# Water_SCH.net
KiCad netlist of a schematic drawn in Altium Designer
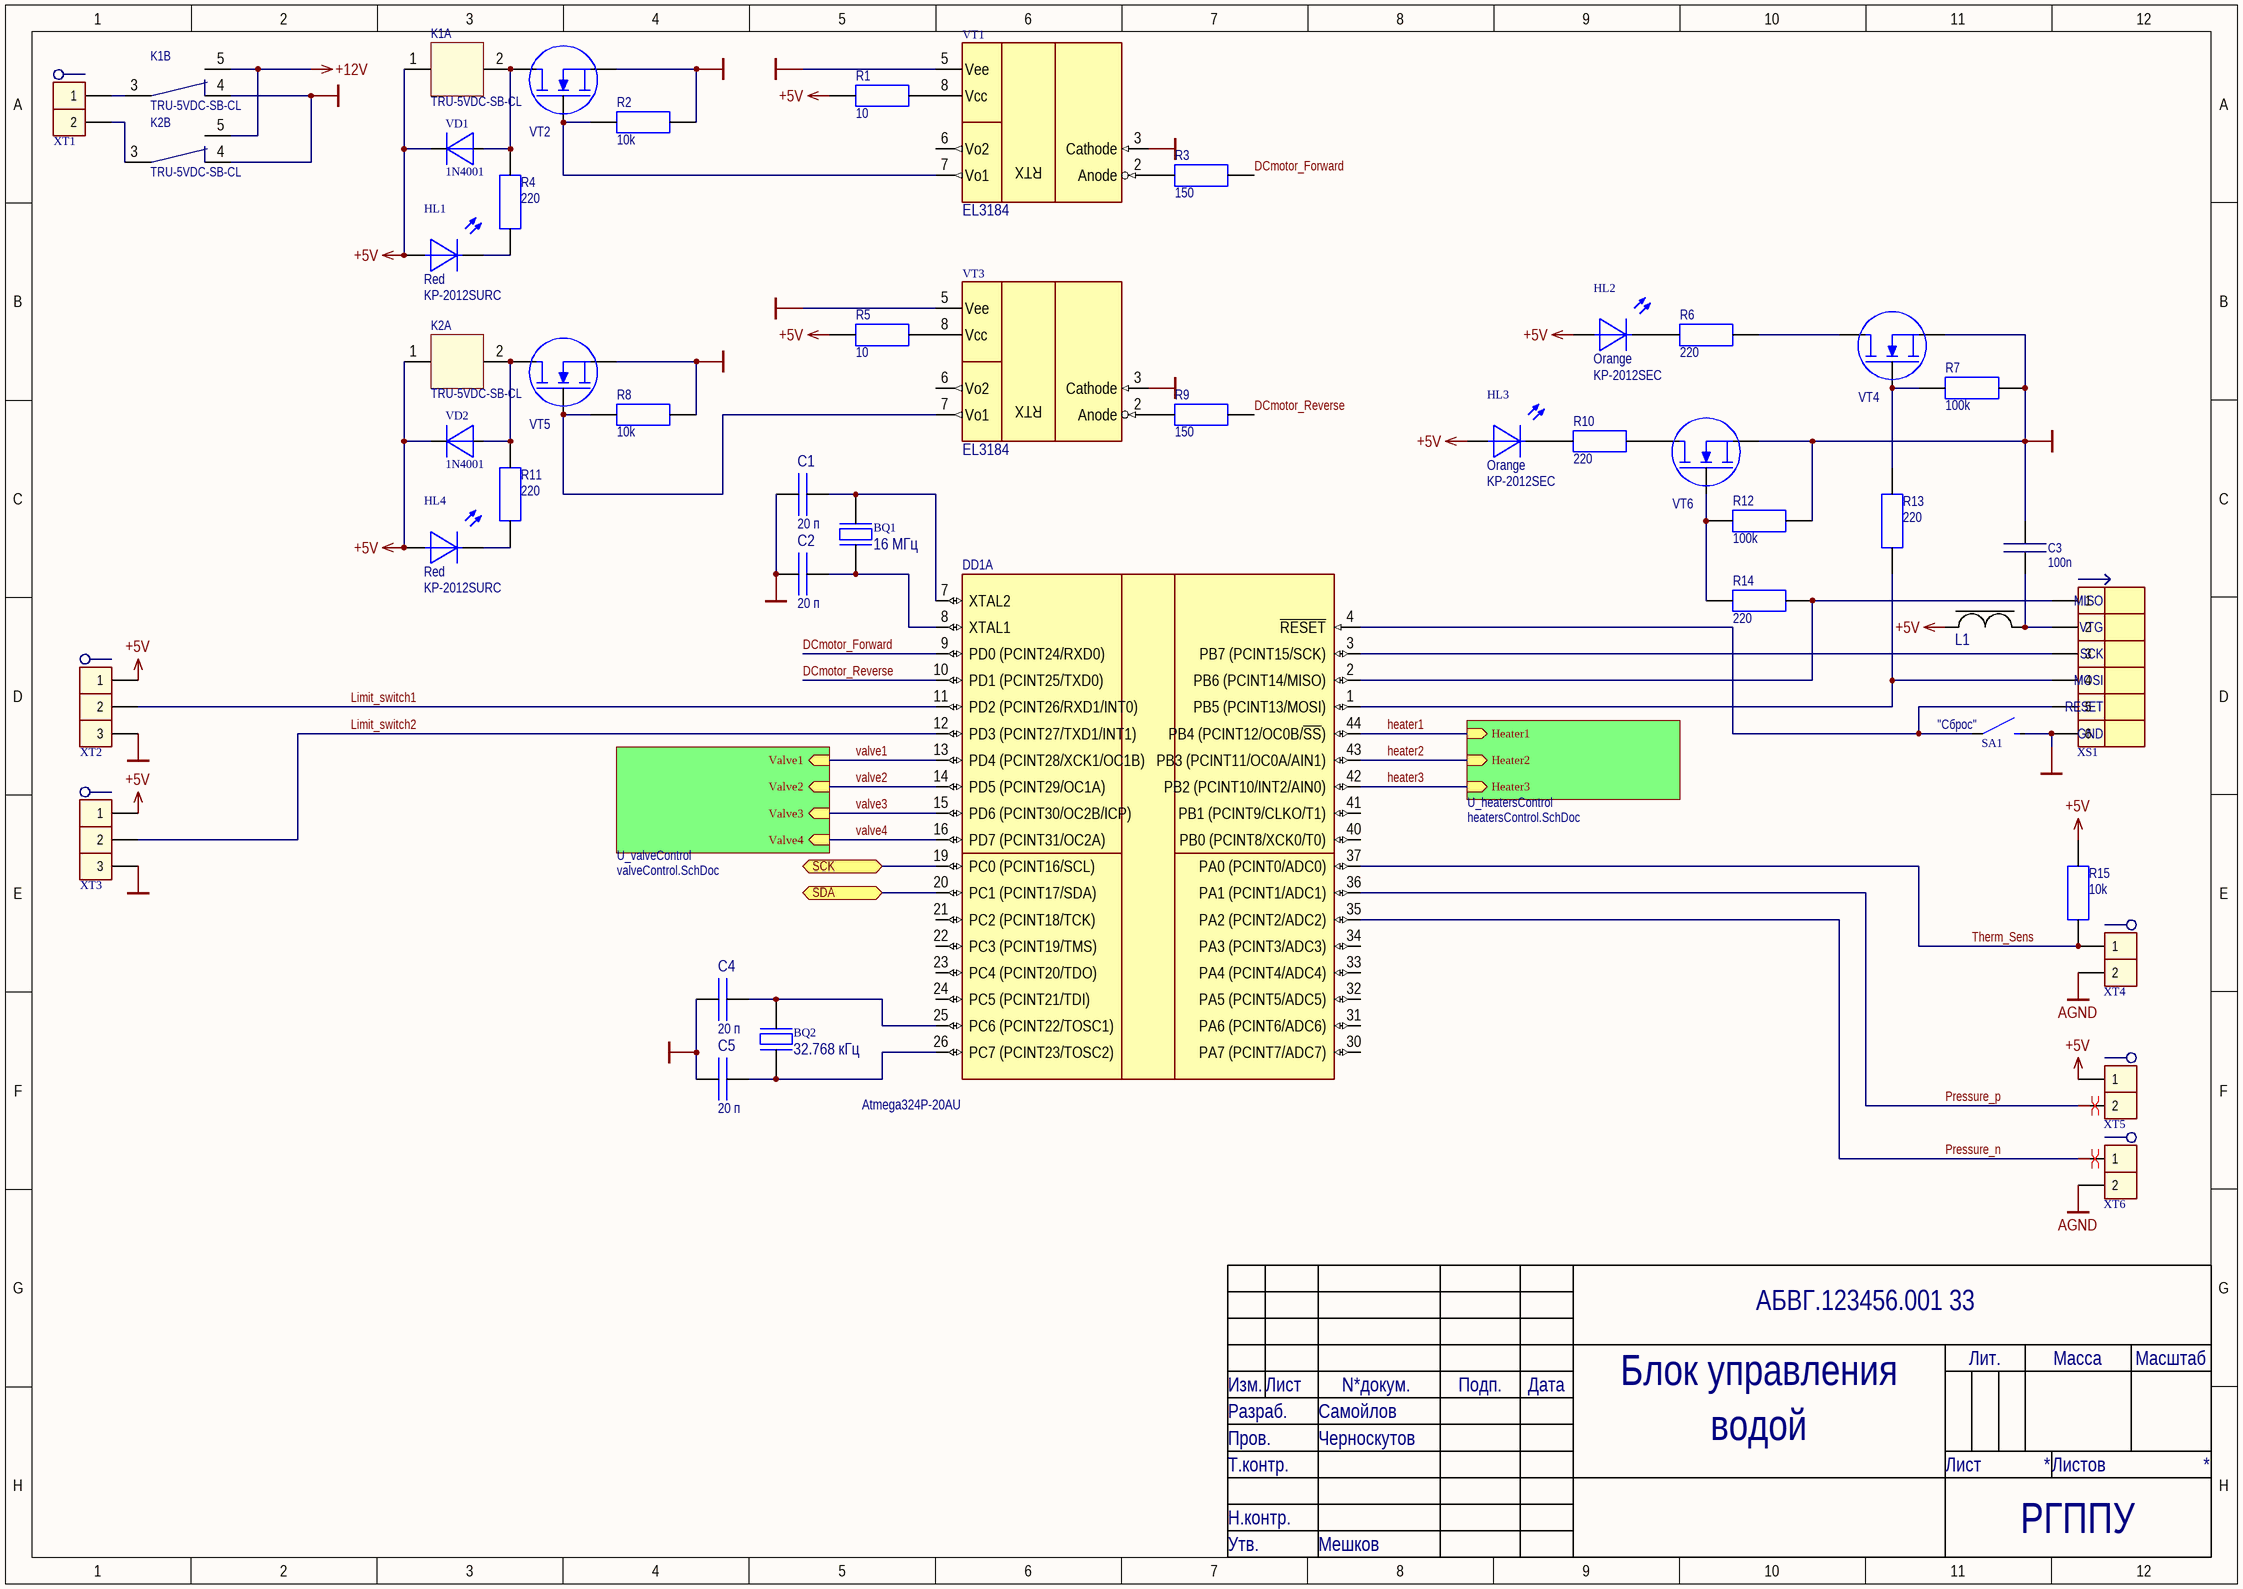
[diagram p0: Water_SCH.SchDoc]

(export (version "E")
  (design (tool "Eeschema 10.0.6"))
  (components
    (comp (ref "BQ1")
      (value "16 МГц")
      (footprint "Piezoelectric:HC-49/S")
      (description "Piezoelectric elements")
      (fields
        (field (name "MANUFACTURER") "Taizhou")
        (field (name "MANUFACTURERPARTNUMBER") "16000 кГц 20ppm 20pF")
      )
      (libsource (lib "Piezoelectric") (part "Piezoelectric_16000"))
    )
    (comp (ref "BQ2")
      (value "32.768 кГц")
      (footprint "Piezoelectric:HC-49/S")
      (description "Piezoelectric elements")
      (fields
        (field (name "MANUFACTURER") "Taizhou")
        (field (name "MANUFACTURERPARTNUMBER") "16000 кГц 20ppm 20pF")
      )
      (libsource (lib "Piezoelectric") (part "Piezoelectric_16000"))
    )
    (comp (ref "C1")
      (value "20 п")
      (footprint "Cap:CAPC3216X05M")
      (description "20pF Bipolar cap")
      (fields
        (field (name "MANUFACTURERPARTNUMBER") "CC0603JRNP09BN200")
        (field (name "MANUFACTURER") "Yageo")
      )
      (libsource (lib "Cap") (part "p00020_050"))
    )
    (comp (ref "C2")
      (value "20 п")
      (footprint "Cap:CAPC3216X05M")
      (description "20pF Bipolar cap")
      (fields
        (field (name "MANUFACTURERPARTNUMBER") "CC0603JRNP09BN200")
        (field (name "MANUFACTURER") "Yageo")
      )
      (libsource (lib "Cap") (part "p00020_050"))
    )
    (comp (ref "C3")
      (value "100n")
      (footprint "SMDRC0805")
      (description "Generic capasitor non-polar")
      (fields (field (name "PARTNUMBER") "Capacitor 0805 100n"))
      (libsource (lib "library") (part "Capacitor"))
    )
    (comp (ref "C4")
      (value "20 п")
      (footprint "Cap:CAPC3216X05M")
      (description "20pF Bipolar cap")
      (fields
        (field (name "MANUFACTURERPARTNUMBER") "CC0603JRNP09BN200")
        (field (name "MANUFACTURER") "Yageo")
      )
      (libsource (lib "Cap") (part "p00020_050"))
    )
    (comp (ref "C5")
      (value "20 п")
      (footprint "Cap:CAPC3216X05M")
      (description "20pF Bipolar cap")
      (fields
        (field (name "MANUFACTURERPARTNUMBER") "CC0603JRNP09BN200")
        (field (name "MANUFACTURER") "Yageo")
      )
      (libsource (lib "Cap") (part "p00020_050"))
    )
    (comp (ref "DD1")
      (value "Atmega324P-20AU")
      (footprint "Atmel Microcontroller 8-Bit Automotive AVR:44ML_M")
      (description "Microcontroller 8-bit")
      (fields (field (name "MANUFACTURER") "Atmel") (field (name "MANUFACTURERPARTNUMBER") "Atmega324P-20AU"))
      (libsource (lib "Microcontrollers") (part "Atmega324P-20AU"))
    )
    (comp (ref "HL1")
      (value "Red")
      (footprint "Indicator:DIOMELF2012M")
      (description "Diod LED SMD Red")
      (fields (field (name "MANUFACTURERPARTNUMBER") "KP-2012SURC"))
      (libsource (lib "Indicator") (part "LED1_R"))
    )
    (comp (ref "HL2")
      (value "Orange")
      (footprint "Indicator:DIOMELF2012M")
      (description "Diod LED SMD Orange")
      (fields (field (name "MANUFACTURERPARTNUMBER") "KP-2012SEC"))
      (libsource (lib "Indicator") (part "LED1_O"))
    )
    (comp (ref "HL3")
      (value "Orange")
      (footprint "Indicator:DIOMELF2012M")
      (description "Diod LED SMD Orange")
      (fields (field (name "MANUFACTURERPARTNUMBER") "KP-2012SEC"))
      (libsource (lib "Indicator") (part "LED1_O"))
    )
    (comp (ref "HL4")
      (value "Red")
      (footprint "Indicator:DIOMELF2012M")
      (description "Diod LED SMD Red")
      (fields (field (name "MANUFACTURERPARTNUMBER") "KP-2012SURC"))
      (libsource (lib "Indicator") (part "LED1_R"))
    )
    (comp (ref "K1")
      (value "TRU-5VDC-SB-CL")
      (footprint "Switch:TRU-5VDC-SB-CL")
      (libsource (lib "Switch") (part "TRU-5VDC-SB-CL"))
    )
    (comp (ref "K2")
      (value "TRU-5VDC-SB-CL")
      (footprint "Switch:TRU-5VDC-SB-CL")
      (libsource (lib "Switch") (part "TRU-5VDC-SB-CL"))
    )
    (comp (ref "L1")
      (value "MPZ1608S181A")
      (footprint "Inductor:INDC0603X03M")
      (description "Ferrite Bead")
      (libsource (lib "Inductor") (part "Ferrite Bead"))
    )
    (comp (ref "R1")
      (value "10")
      (footprint "SMDRC0805")
      (description "Generic resistor")
      (fields (field (name "PARTNUMBER") "Resistor 0805 10"))
      (libsource (lib "library") (part "Resistor"))
    )
    (comp (ref "R2")
      (value "10k")
      (footprint "SMDRC0805")
      (description "Generic resistor")
      (fields (field (name "PARTNUMBER") "Resistor 0805 10k"))
      (libsource (lib "") (part "Resistor_2"))
    )
    (comp (ref "R3")
      (value "150")
      (footprint "SMDRC0805")
      (description "Generic resistor")
      (fields (field (name "PARTNUMBER") "Resistor 0805 150"))
      (libsource (lib "library") (part "Resistor"))
    )
    (comp (ref "R4")
      (value "220")
      (footprint "SMDRC0805")
      (description "Generic resistor")
      (fields (field (name "PARTNUMBER") "Resistor 0805 220"))
      (libsource (lib "") (part "Resistor_1"))
    )
    (comp (ref "R5")
      (value "10")
      (footprint "SMDRC0805")
      (description "Generic resistor")
      (fields (field (name "PARTNUMBER") "Resistor 0805 10"))
      (libsource (lib "library") (part "Resistor"))
    )
    (comp (ref "R6")
      (value "220")
      (footprint "SMDRC0805")
      (description "Generic resistor")
      (fields (field (name "PARTNUMBER") "Resistor 0805 220"))
      (libsource (lib "library") (part "Resistor"))
    )
    (comp (ref "R7")
      (value "100k")
      (footprint "SMDRC0805")
      (description "Generic resistor")
      (fields (field (name "PARTNUMBER") "Resistor 0805 100k"))
      (libsource (lib "") (part "Resistor_2"))
    )
    (comp (ref "R8")
      (value "10k")
      (footprint "SMDRC0805")
      (description "Generic resistor")
      (fields (field (name "PARTNUMBER") "Resistor 0805 10k"))
      (libsource (lib "") (part "Resistor_2"))
    )
    (comp (ref "R9")
      (value "150")
      (footprint "SMDRC0805")
      (description "Generic resistor")
      (fields (field (name "PARTNUMBER") "Resistor 0805 150"))
      (libsource (lib "library") (part "Resistor"))
    )
    (comp (ref "R10")
      (value "220")
      (footprint "SMDRC0805")
      (description "Generic resistor")
      (fields (field (name "PARTNUMBER") "Resistor 0805 220"))
      (libsource (lib "library") (part "Resistor"))
    )
    (comp (ref "R11")
      (value "220")
      (footprint "SMDRC0805")
      (description "Generic resistor")
      (fields (field (name "PARTNUMBER") "Resistor 0805 220"))
      (libsource (lib "") (part "Resistor_1"))
    )
    (comp (ref "R12")
      (value "100k")
      (footprint "SMDRC0805")
      (description "Generic resistor")
      (fields (field (name "PARTNUMBER") "Resistor 0805 100k"))
      (libsource (lib "") (part "Resistor_2"))
    )
    (comp (ref "R13")
      (value "220")
      (footprint "SMDRC0805")
      (description "Generic resistor")
      (fields (field (name "PARTNUMBER") "Resistor 0805 220"))
      (libsource (lib "") (part "Resistor_3"))
    )
    (comp (ref "R14")
      (value "220")
      (footprint "SMDRC0805")
      (description "Generic resistor")
      (fields (field (name "PARTNUMBER") "Resistor 0805 220"))
      (libsource (lib "library") (part "Resistor"))
    )
    (comp (ref "R15")
      (value "10k")
      (footprint "SMDRC0805")
      (description "Generic resistor")
      (fields (field (name "PARTNUMBER") "Resistor 0805 10k"))
      (libsource (lib "") (part "Resistor_2"))
    )
    (comp (ref "SA1")
      (value "DTSM20-4.3")
      (footprint "Switch:DTSM20")
      (description "Switch open")
      (fields (field (name "MANUFACTURER") "Diptronics"))
      (libsource (lib "Switch") (part "Switch1_DTSM20-4.3"))
    )
    (comp (ref "VD1")
      (value "1N4001")
      (footprint "DIod:PinDiode")
      (description "Rectifying diode")
      (fields (field (name "MANUFACTURERPARTNUMBER") "1N4001"))
      (libsource (lib "Diod") (part "1N4001"))
    )
    (comp (ref "VD2")
      (value "1N4001")
      (footprint "DIod:PinDiode")
      (description "Rectifying diode")
      (fields (field (name "MANUFACTURERPARTNUMBER") "1N4001"))
      (libsource (lib "Diod") (part "1N4001"))
    )
    (comp (ref "VT1")
      (value "EL3184")
      (footprint "DIP8")
      (description "Optocouple IGBT driver")
      (fields
        (field (name "MANUFACTURER") "Everlight Electronics Co. Ltd")
        (field (name "MANUFACTURERPARTNUMBER") "EL3184")
      )
      (libsource (lib "Interface") (part "EL3184"))
    )
    (comp (ref "VT2")
      (value "2N7002")
      (footprint "Standard:SOT23 (TO-236AB)")
      (description "60V, 300mA N-channel Trench MOSFET")
      (libsource (lib "Transistor") (part "2N7002 n-MOSFET"))
    )
    (comp (ref "VT3")
      (value "EL3184")
      (footprint "DIP8")
      (description "Optocouple IGBT driver")
      (fields
        (field (name "MANUFACTURER") "Everlight Electronics Co. Ltd")
        (field (name "MANUFACTURERPARTNUMBER") "EL3184")
      )
      (libsource (lib "Interface") (part "EL3184"))
    )
    (comp (ref "VT4")
      (value "2N7002")
      (footprint "Standard:SOT23 (TO-236AB)")
      (description "60V, 300mA N-channel Trench MOSFET")
      (libsource (lib "Transistor") (part "2N7002 n-MOSFET"))
    )
    (comp (ref "VT5")
      (value "2N7002")
      (footprint "Standard:SOT23 (TO-236AB)")
      (description "60V, 300mA N-channel Trench MOSFET")
      (libsource (lib "Transistor") (part "2N7002 n-MOSFET"))
    )
    (comp (ref "VT6")
      (value "2N7002")
      (footprint "Standard:SOT23 (TO-236AB)")
      (description "60V, 300mA N-channel Trench MOSFET")
      (libsource (lib "Transistor") (part "2N7002 n-MOSFET"))
    )
    (comp (ref "XS1")
      (value "IDC-06M")
      (footprint "Connector:IDC-06M")
      (description "SPI connector")
      (libsource (lib "Connector") (part "Con6_M IDC-06M_SPI"))
    )
    (comp (ref "XT1")
      (value "330-021-12")
      (footprint "Connector:330-021-12")
      (description "Demountable connection  2-pin")
      (fields (field (name "MANUFACTURER") "Degson Electronics Co., Ltd"))
      (libsource (lib "") (part "Con2_D 330-021-12_1"))
    )
    (comp (ref "XT2")
      (value "330-031-12")
      (footprint "Connector:330-031-12")
      (description "Demountable connection 3-pin")
      (fields (field (name "MANUFACTURER") "Degson Electronics Co., Ltd"))
      (libsource (lib "Connector") (part "Con3_D 330-031-12"))
    )
    (comp (ref "XT3")
      (value "330-031-12")
      (footprint "Connector:330-031-12")
      (description "Demountable connection 3-pin")
      (fields (field (name "MANUFACTURER") "Degson Electronics Co., Ltd"))
      (libsource (lib "Connector") (part "Con3_D 330-031-12"))
    )
    (comp (ref "XT4")
      (value "330-021-12")
      (footprint "Connector:330-021-12")
      (description "Demountable connection  2-pin")
      (fields (field (name "MANUFACTURER") "Degson Electronics Co., Ltd"))
      (libsource (lib "Connector") (part "Con2_D 330-021-12"))
    )
    (comp (ref "XT5")
      (value "330-021-12")
      (footprint "Connector:330-021-12")
      (description "Demountable connection  2-pin")
      (fields (field (name "MANUFACTURER") "Degson Electronics Co., Ltd"))
      (libsource (lib "Connector") (part "Con2_D 330-021-12"))
    )
    (comp (ref "XT6")
      (value "330-021-12")
      (footprint "Connector:330-021-12")
      (description "Demountable connection  2-pin")
      (fields (field (name "MANUFACTURER") "Degson Electronics Co., Ltd"))
      (libsource (lib "Connector") (part "Con2_D 330-021-12"))
    )
  )
  (nets
    (net (code "1") (name "+5V") (class "Default")
      (node (ref "HL1") (pin "1") (pinfunction "1_1") (pintype "passive"))
      (node (ref "HL2") (pin "1") (pinfunction "1_1") (pintype "passive"))
      (node (ref "HL3") (pin "1") (pinfunction "1_1") (pintype "passive"))
      (node (ref "HL4") (pin "1") (pinfunction "1_1") (pintype "passive"))
      (node (ref "K1") (pin "1") (pinfunction "1_1") (pintype "passive"))
      (node (ref "K2") (pin "1") (pinfunction "1_1") (pintype "passive"))
      (node (ref "L1") (pin "1") (pinfunction "1_1") (pintype "passive"))
      (node (ref "R1") (pin "2") (pinfunction "2_2") (pintype "passive"))
      (node (ref "R15") (pin "2") (pinfunction "2_2") (pintype "passive"))
      (node (ref "R5") (pin "2") (pinfunction "2_2") (pintype "passive"))
      (node (ref "VD1") (pin "K") (pinfunction "K_K") (pintype "passive"))
      (node (ref "VD2") (pin "K") (pinfunction "K_K") (pintype "passive"))
      (node (ref "XT2") (pin "1") (pinfunction "1_1") (pintype "passive"))
      (node (ref "XT3") (pin "1") (pinfunction "1_1") (pintype "passive"))
      (node (ref "XT5") (pin "1") (pinfunction "1_1") (pintype "passive"))
    )
    (net (code "2") (name "+12V") (class "Default")
      (node (ref "K1") (pin "5") (pinfunction "5_5") (pintype "passive"))
      (node (ref "K2") (pin "5") (pinfunction "5_5") (pintype "passive"))
    )
    (net (code "3") (name "/DCmotor_Forward") (class "Default")
      (node (ref "DD1") (pin "9") (pinfunction "PD0_(PCINT24/RXD0)_9") (pintype "bidirectional"))
      (node (ref "R3") (pin "1") (pinfunction "1_1") (pintype "passive"))
    )
    (net (code "4") (name "/DCmotor_Reverse") (class "Default")
      (node (ref "DD1") (pin "10") (pinfunction "PD1_(PCINT25/TXD0)_10") (pintype "bidirectional"))
      (node (ref "R9") (pin "1") (pinfunction "1_1") (pintype "passive"))
    )
    (net (code "5") (name "/Limit_switch1") (class "Default")
      (node (ref "DD1") (pin "11") (pinfunction "PD2_(PCINT26/RXD1/INT0)_11") (pintype "bidirectional"))
      (node (ref "XT2") (pin "2") (pinfunction "2_2") (pintype "passive"))
    )
    (net (code "6") (name "/Limit_switch2") (class "Default")
      (node (ref "DD1") (pin "12") (pinfunction "PD3_(PCINT27/TXD1/INT1)_12") (pintype "bidirectional"))
      (node (ref "XT3") (pin "2") (pinfunction "2_2") (pintype "passive"))
    )
    (net (code "7") (name "/Pressure_n") (class "Default")
      (node (ref "DD1") (pin "35") (pinfunction "PA2_(PCINT2/ADC2)_35") (pintype "bidirectional"))
      (node (ref "XT6") (pin "1") (pinfunction "1_1") (pintype "passive"))
    )
    (net (code "8") (name "/Pressure_p") (class "Default")
      (node (ref "DD1") (pin "36") (pinfunction "PA1_(PCINT1/ADC1)_36") (pintype "bidirectional"))
      (node (ref "XT5") (pin "2") (pinfunction "2_2") (pintype "passive"))
    )
    (net (code "9") (name "/SCK") (class "Default")
      (node (ref "DD1") (pin "19") (pinfunction "PC0_(PCINT16/SCL)_19") (pintype "bidirectional"))
    )
    (net (code "10") (name "/SDA") (class "Default")
      (node (ref "DD1") (pin "20") (pinfunction "PC1_(PCINT17/SDA)_20") (pintype "bidirectional"))
    )
    (net (code "11") (name "/Therm_Sens") (class "Default")
      (node (ref "DD1") (pin "37") (pinfunction "PA0_(PCINT0/ADC0)_37") (pintype "bidirectional"))
      (node (ref "R15") (pin "1") (pinfunction "1_1") (pintype "passive"))
      (node (ref "XT4") (pin "1") (pinfunction "1_1") (pintype "passive"))
    )
    (net (code "12") (name "/heater1") (class "Default")
      (node (ref "DD1") (pin "44") (pinfunction "PB4_(PCINT12/OC0B/~{SS})_44") (pintype "bidirectional"))
    )
    (net (code "13") (name "/heater2") (class "Default")
      (node (ref "DD1") (pin "43") (pinfunction "PB3_(PCINT11/OC0A/AIN1)_43") (pintype "bidirectional"))
    )
    (net (code "14") (name "/heater3") (class "Default")
      (node (ref "DD1") (pin "42") (pinfunction "PB2_(PCINT10/INT2/AIN0)_42") (pintype "bidirectional"))
    )
    (net (code "15") (name "/valve1") (class "Default")
      (node (ref "DD1") (pin "13") (pinfunction "PD4_(PCINT28/XCK1/OC1B)_13") (pintype "bidirectional"))
    )
    (net (code "16") (name "/valve2") (class "Default")
      (node (ref "DD1") (pin "14") (pinfunction "PD5_(PCINT29/OC1A)_14") (pintype "bidirectional"))
    )
    (net (code "17") (name "/valve3") (class "Default")
      (node (ref "DD1") (pin "15") (pinfunction "PD6_(PCINT30/OC2B/ICP)_15") (pintype "bidirectional"))
    )
    (net (code "18") (name "/valve4") (class "Default")
      (node (ref "DD1") (pin "16") (pinfunction "PD7_(PCINT31/OC2A)_16") (pintype "bidirectional"))
    )
    (net (code "19") (name "AGND") (class "Default")
      (node (ref "XT4") (pin "2") (pinfunction "2_2") (pintype "passive"))
      (node (ref "XT6") (pin "2") (pinfunction "2_2") (pintype "passive"))
    )
    (net (code "20") (name "GND") (class "Default")
      (node (ref "C1") (pin "2") (pinfunction "2_2") (pintype "passive"))
      (node (ref "C2") (pin "2") (pinfunction "2_2") (pintype "passive"))
      (node (ref "C3") (pin "2") (pintype "passive"))
      (node (ref "C4") (pin "2") (pinfunction "2_2") (pintype "passive"))
      (node (ref "C5") (pin "2") (pinfunction "2_2") (pintype "passive"))
      (node (ref "K1") (pin "4") (pinfunction "4_4") (pintype "passive"))
      (node (ref "K2") (pin "4") (pinfunction "4_4") (pintype "passive"))
      (node (ref "R12") (pin "2") (pinfunction "2_2") (pintype "passive"))
      (node (ref "R2") (pin "2") (pinfunction "2_2") (pintype "passive"))
      (node (ref "R7") (pin "2") (pinfunction "2_2") (pintype "passive"))
      (node (ref "R8") (pin "2") (pinfunction "2_2") (pintype "passive"))
      (node (ref "SA1") (pin "2") (pinfunction "2_2") (pintype "passive"))
      (node (ref "VT1") (pin "3") (pinfunction "Cathode_3") (pintype "input"))
      (node (ref "VT1") (pin "5") (pinfunction "Vee_5") (pintype "power_in"))
      (node (ref "VT2") (pin "2") (pinfunction "S_2") (pintype "passive"))
      (node (ref "VT3") (pin "3") (pinfunction "Cathode_3") (pintype "input"))
      (node (ref "VT3") (pin "5") (pinfunction "Vee_5") (pintype "power_in"))
      (node (ref "VT4") (pin "2") (pinfunction "S_2") (pintype "passive"))
      (node (ref "VT5") (pin "2") (pinfunction "S_2") (pintype "passive"))
      (node (ref "VT6") (pin "2") (pinfunction "S_2") (pintype "passive"))
      (node (ref "XS1") (pin "6") (pinfunction "6_6") (pintype "passive"))
      (node (ref "XT2") (pin "3") (pinfunction "3_3") (pintype "passive"))
      (node (ref "XT3") (pin "3") (pinfunction "3_3") (pintype "passive"))
    )
    (net (code "21") (name "Net-(C3-Pad1)") (class "Default")
      (node (ref "C3") (pin "1") (pintype "passive"))
      (node (ref "L1") (pin "2") (pinfunction "2_2") (pintype "passive"))
      (node (ref "XS1") (pin "2") (pinfunction "2_2") (pintype "passive"))
    )
    (net (code "22") (name "Net-(DD1A-PB5_(PCINT13{slash}MOSI))") (class "Default")
      (node (ref "DD1") (pin "1") (pinfunction "PB5_(PCINT13/MOSI)_1") (pintype "bidirectional"))
      (node (ref "R13") (pin "1") (pinfunction "1_1") (pintype "passive"))
      (node (ref "XS1") (pin "4") (pinfunction "4_4") (pintype "passive"))
    )
    (net (code "23") (name "Net-(DD1A-PB6_(PCINT14{slash}MISO))") (class "Default")
      (node (ref "DD1") (pin "2") (pinfunction "PB6_(PCINT14/MISO)_2") (pintype "bidirectional"))
      (node (ref "R14") (pin "1") (pinfunction "1_1") (pintype "passive"))
      (node (ref "XS1") (pin "1") (pinfunction "1_1") (pintype "passive"))
    )
    (net (code "24") (name "Net-(DD1A-PB7_(PCINT15{slash}SCK))") (class "Default")
      (node (ref "DD1") (pin "3") (pinfunction "PB7_(PCINT15/SCK)_3") (pintype "bidirectional"))
      (node (ref "XS1") (pin "3") (pinfunction "3_3") (pintype "passive"))
    )
    (net (code "25") (name "Net-(DD1A-PC6_(PCINT22{slash}TOSC1))") (class "Default")
      (node (ref "BQ2") (pin "2") (pinfunction "2_2") (pintype "passive"))
      (node (ref "C4") (pin "1") (pinfunction "1_1") (pintype "passive"))
      (node (ref "DD1") (pin "25") (pinfunction "PC6_(PCINT22/TOSC1)_25") (pintype "bidirectional"))
    )
    (net (code "26") (name "Net-(DD1A-PC7_(PCINT23{slash}TOSC2))") (class "Default")
      (node (ref "BQ2") (pin "1") (pinfunction "1_1") (pintype "passive"))
      (node (ref "C5") (pin "1") (pinfunction "1_1") (pintype "passive"))
      (node (ref "DD1") (pin "26") (pinfunction "PC7_(PCINT23/TOSC2)_26") (pintype "bidirectional"))
    )
    (net (code "27") (name "Net-(DD1A-XTAL1)") (class "Default")
      (node (ref "BQ1") (pin "1") (pinfunction "1_1") (pintype "passive"))
      (node (ref "C2") (pin "1") (pinfunction "1_1") (pintype "passive"))
      (node (ref "DD1") (pin "8") (pinfunction "XTAL1_8") (pintype "bidirectional"))
    )
    (net (code "28") (name "Net-(DD1A-XTAL2)") (class "Default")
      (node (ref "BQ1") (pin "2") (pinfunction "2_2") (pintype "passive"))
      (node (ref "C1") (pin "1") (pinfunction "1_1") (pintype "passive"))
      (node (ref "DD1") (pin "7") (pinfunction "XTAL2_7") (pintype "bidirectional"))
    )
    (net (code "29") (name "Net-(DD1A-~{RESET})") (class "Default")
      (node (ref "DD1") (pin "4") (pinfunction "~{RESET}_4") (pintype "input"))
      (node (ref "SA1") (pin "1") (pinfunction "1_1") (pintype "passive"))
      (node (ref "XS1") (pin "5") (pinfunction "5_5") (pintype "passive"))
    )
    (net (code "30") (name "Net-(HL1-Pad2)") (class "Default")
      (node (ref "HL1") (pin "2") (pinfunction "2_2") (pintype "passive"))
      (node (ref "R4") (pin "2") (pinfunction "2_2") (pintype "passive"))
    )
    (net (code "31") (name "Net-(HL2-Pad2)") (class "Default")
      (node (ref "HL2") (pin "2") (pinfunction "2_2") (pintype "passive"))
      (node (ref "R6") (pin "2") (pinfunction "2_2") (pintype "passive"))
    )
    (net (code "32") (name "Net-(HL3-Pad2)") (class "Default")
      (node (ref "HL3") (pin "2") (pinfunction "2_2") (pintype "passive"))
      (node (ref "R10") (pin "2") (pinfunction "2_2") (pintype "passive"))
    )
    (net (code "33") (name "Net-(HL4-Pad2)") (class "Default")
      (node (ref "HL4") (pin "2") (pinfunction "2_2") (pintype "passive"))
      (node (ref "R11") (pin "2") (pinfunction "2_2") (pintype "passive"))
    )
    (net (code "34") (name "Net-(K1-Pad3)") (class "Default")
      (node (ref "K1") (pin "3") (pinfunction "3_3") (pintype "passive"))
      (node (ref "XT1") (pin "1") (pinfunction "1_1") (pintype "passive"))
    )
    (net (code "35") (name "Net-(K2-Pad3)") (class "Default")
      (node (ref "K2") (pin "3") (pinfunction "3_3") (pintype "passive"))
      (node (ref "XT1") (pin "2") (pinfunction "2_2") (pintype "passive"))
    )
    (net (code "36") (name "Net-(VT1-Anode)") (class "Default")
      (node (ref "R3") (pin "2") (pinfunction "2_2") (pintype "passive"))
      (node (ref "VT1") (pin "2") (pinfunction "Anode_2") (pintype "input"))
    )
    (net (code "37") (name "Net-(VT1-Vcc)") (class "Default")
      (node (ref "R1") (pin "1") (pinfunction "1_1") (pintype "passive"))
      (node (ref "VT1") (pin "8") (pinfunction "Vcc_8") (pintype "power_in"))
    )
    (net (code "38") (name "Net-(VT1-Vo1)") (class "Default")
      (node (ref "R2") (pin "1") (pinfunction "1_1") (pintype "passive"))
      (node (ref "VT1") (pin "7") (pinfunction "Vo1_7") (pintype "output"))
      (node (ref "VT2") (pin "1") (pinfunction "G_1") (pintype "passive"))
    )
    (net (code "39") (name "Net-(VT2-D)") (class "Default")
      (node (ref "K1") (pin "2") (pinfunction "2_2") (pintype "passive"))
      (node (ref "R4") (pin "1") (pinfunction "1_1") (pintype "passive"))
      (node (ref "VD1") (pin "A") (pinfunction "A_A") (pintype "passive"))
      (node (ref "VT2") (pin "3") (pinfunction "D_3") (pintype "passive"))
    )
    (net (code "40") (name "Net-(VT3-Anode)") (class "Default")
      (node (ref "R9") (pin "2") (pinfunction "2_2") (pintype "passive"))
      (node (ref "VT3") (pin "2") (pinfunction "Anode_2") (pintype "input"))
    )
    (net (code "41") (name "Net-(VT3-Vcc)") (class "Default")
      (node (ref "R5") (pin "1") (pinfunction "1_1") (pintype "passive"))
      (node (ref "VT3") (pin "8") (pinfunction "Vcc_8") (pintype "power_in"))
    )
    (net (code "42") (name "Net-(VT3-Vo1)") (class "Default")
      (node (ref "R8") (pin "1") (pinfunction "1_1") (pintype "passive"))
      (node (ref "VT3") (pin "7") (pinfunction "Vo1_7") (pintype "output"))
      (node (ref "VT5") (pin "1") (pinfunction "G_1") (pintype "passive"))
    )
    (net (code "43") (name "Net-(VT4-D)") (class "Default")
      (node (ref "R6") (pin "1") (pinfunction "1_1") (pintype "passive"))
      (node (ref "VT4") (pin "3") (pinfunction "D_3") (pintype "passive"))
    )
    (net (code "44") (name "Net-(VT4-G)") (class "Default")
      (node (ref "R13") (pin "2") (pinfunction "2_2") (pintype "passive"))
      (node (ref "R7") (pin "1") (pinfunction "1_1") (pintype "passive"))
      (node (ref "VT4") (pin "1") (pinfunction "G_1") (pintype "passive"))
    )
    (net (code "45") (name "Net-(VT5-D)") (class "Default")
      (node (ref "K2") (pin "2") (pinfunction "2_2") (pintype "passive"))
      (node (ref "R11") (pin "1") (pinfunction "1_1") (pintype "passive"))
      (node (ref "VD2") (pin "A") (pinfunction "A_A") (pintype "passive"))
      (node (ref "VT5") (pin "3") (pinfunction "D_3") (pintype "passive"))
    )
    (net (code "46") (name "Net-(VT6-D)") (class "Default")
      (node (ref "R10") (pin "1") (pinfunction "1_1") (pintype "passive"))
      (node (ref "VT6") (pin "3") (pinfunction "D_3") (pintype "passive"))
    )
    (net (code "47") (name "Net-(VT6-G)") (class "Default")
      (node (ref "R12") (pin "1") (pinfunction "1_1") (pintype "passive"))
      (node (ref "R14") (pin "2") (pinfunction "2_2") (pintype "passive"))
      (node (ref "VT6") (pin "1") (pinfunction "G_1") (pintype "passive"))
    )
    (net (code "48") (name "unconnected-(DD1A-PA3_(PCINT3{slash}ADC3)-Pad34)") (class "Default")
      (node (ref "DD1") (pin "34") (pinfunction "PA3_(PCINT3/ADC3)_34") (pintype "bidirectional"))
    )
    (net (code "49") (name "unconnected-(DD1A-PA4_(PCINT4{slash}ADC4)-Pad33)") (class "Default")
      (node (ref "DD1") (pin "33") (pinfunction "PA4_(PCINT4/ADC4)_33") (pintype "bidirectional"))
    )
    (net (code "50") (name "unconnected-(DD1A-PA5_(PCINT5{slash}ADC5)-Pad32)") (class "Default")
      (node (ref "DD1") (pin "32") (pinfunction "PA5_(PCINT5/ADC5)_32") (pintype "bidirectional"))
    )
    (net (code "51") (name "unconnected-(DD1A-PA6_(PCINT6{slash}ADC6)-Pad31)") (class "Default")
      (node (ref "DD1") (pin "31") (pinfunction "PA6_(PCINT6/ADC6)_31") (pintype "bidirectional"))
    )
    (net (code "52") (name "unconnected-(DD1A-PA7_(PCINT7{slash}ADC7)-Pad30)") (class "Default")
      (node (ref "DD1") (pin "30") (pinfunction "PA7_(PCINT7/ADC7)_30") (pintype "bidirectional"))
    )
    (net (code "53") (name "unconnected-(DD1A-PB0_(PCINT8{slash}XCK0{slash}T0)-Pad40)") (class "Default")
      (node (ref "DD1") (pin "40") (pinfunction "PB0_(PCINT8/XCK0/T0)_40") (pintype "bidirectional"))
    )
    (net (code "54") (name "unconnected-(DD1A-PB1_(PCINT9{slash}CLKO{slash}T1)-Pad41)") (class "Default")
      (node (ref "DD1") (pin "41") (pinfunction "PB1_(PCINT9/CLKO/T1)_41") (pintype "bidirectional"))
    )
    (net (code "55") (name "unconnected-(DD1A-PC2_(PCINT18{slash}TCK)-Pad21)") (class "Default")
      (node (ref "DD1") (pin "21") (pinfunction "PC2_(PCINT18/TCK)_21") (pintype "bidirectional"))
    )
    (net (code "56") (name "unconnected-(DD1A-PC3_(PCINT19{slash}TMS)-Pad22)") (class "Default")
      (node (ref "DD1") (pin "22") (pinfunction "PC3_(PCINT19/TMS)_22") (pintype "bidirectional"))
    )
    (net (code "57") (name "unconnected-(DD1A-PC4_(PCINT20{slash}TDO)-Pad23)") (class "Default")
      (node (ref "DD1") (pin "23") (pinfunction "PC4_(PCINT20/TDO)_23") (pintype "bidirectional"))
    )
    (net (code "58") (name "unconnected-(DD1A-PC5_(PCINT21{slash}TDI)-Pad24)") (class "Default")
      (node (ref "DD1") (pin "24") (pinfunction "PC5_(PCINT21/TDI)_24") (pintype "bidirectional"))
    )
    (net (code "59") (name "unconnected-(VT1-Vo2-Pad6)") (class "Default")
      (node (ref "VT1") (pin "6") (pinfunction "Vo2_6") (pintype "output"))
    )
    (net (code "60") (name "unconnected-(VT3-Vo2-Pad6)") (class "Default")
      (node (ref "VT3") (pin "6") (pinfunction "Vo2_6") (pintype "output"))
    )
  )
)
